# harp_expander_breakout_v1_0.net
KiCad netlist of a schematic drawn in EAGLE
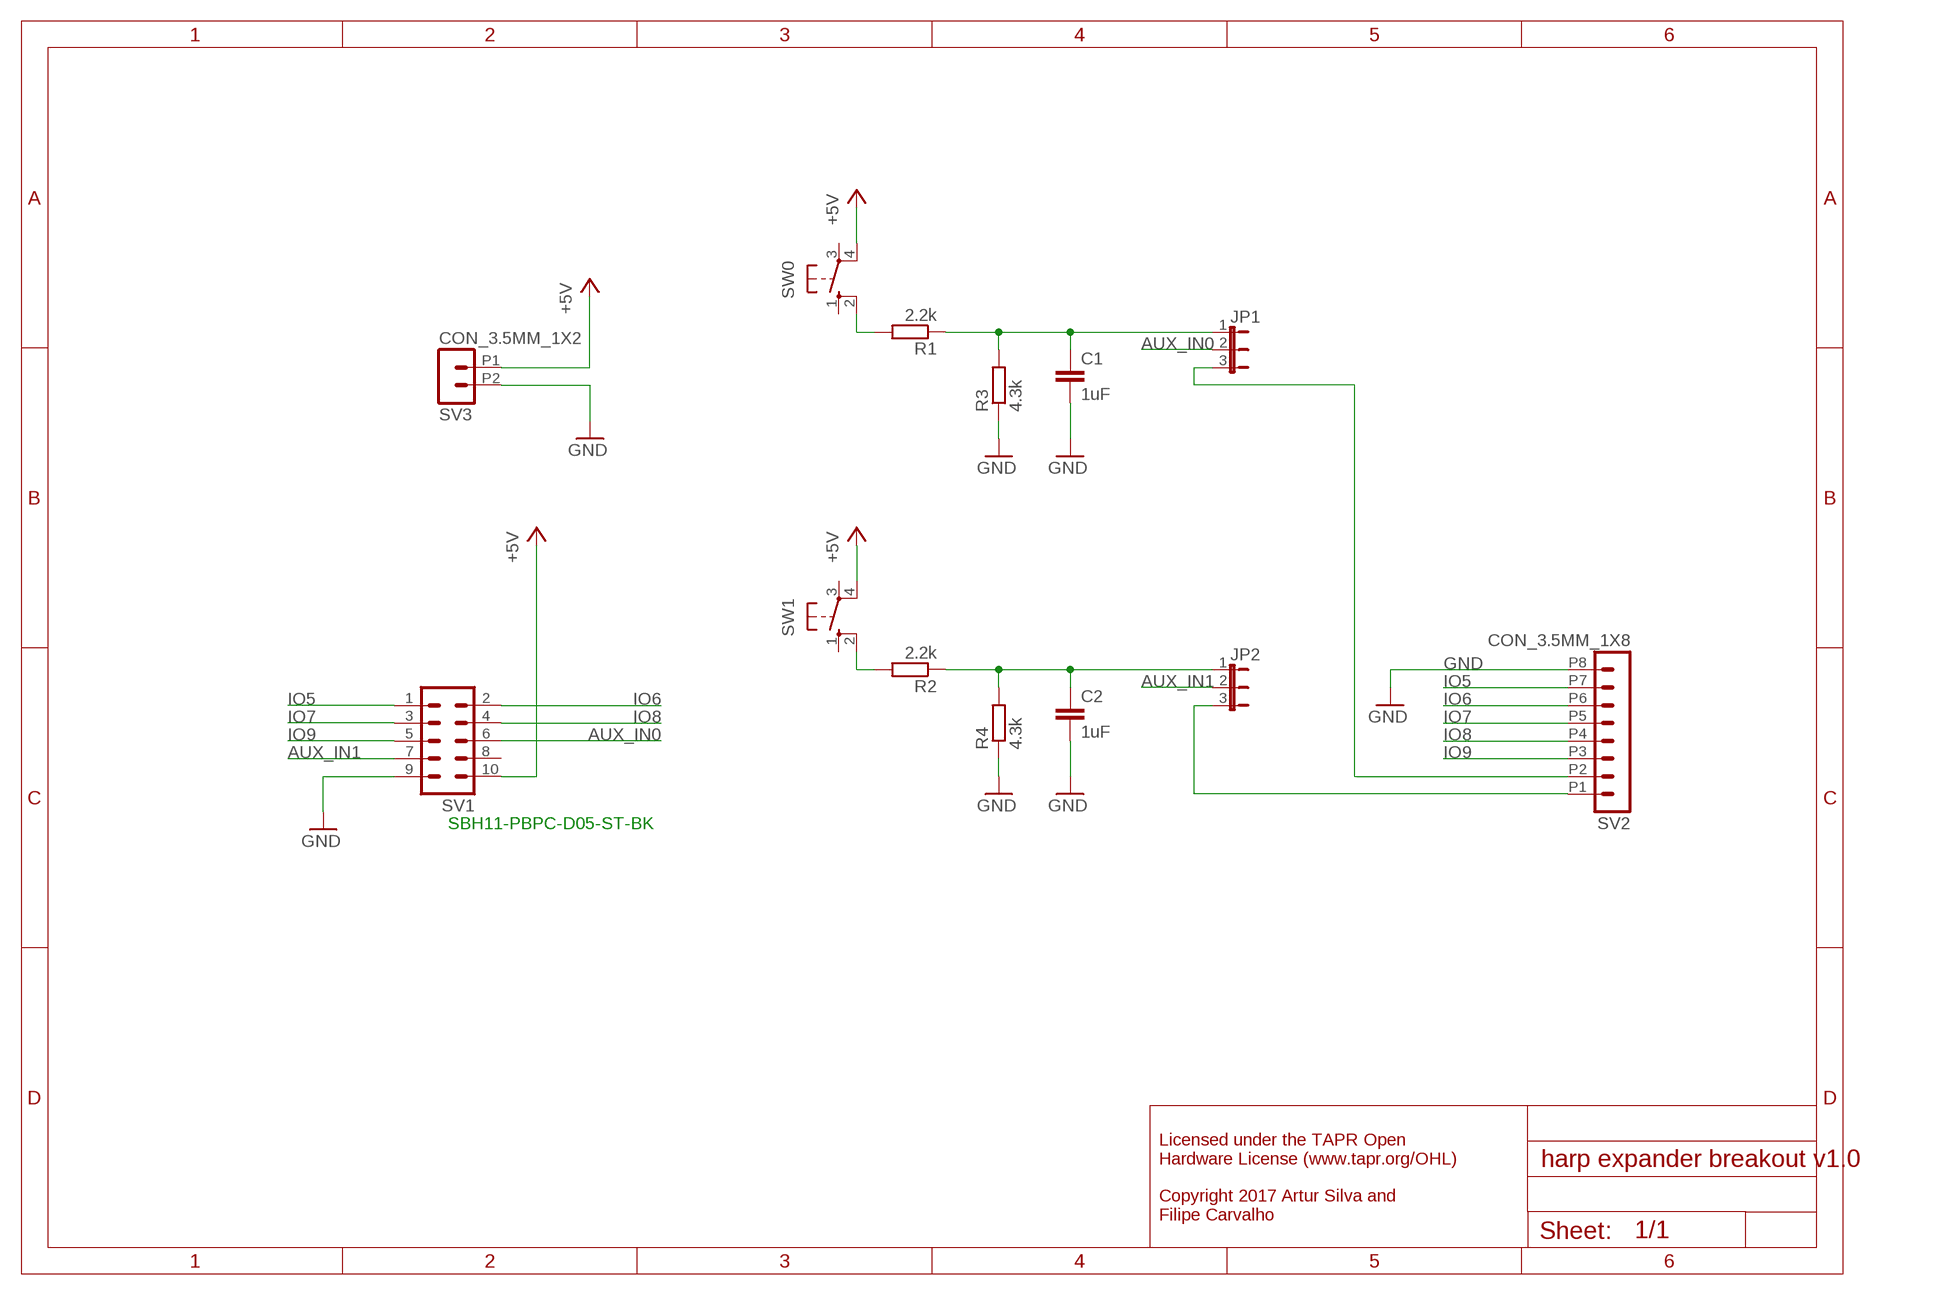
[diagram p0: schematic, sheet 1]

(export (version "E")
  (design (tool "Eeschema 10.0.6"))
  (components
    (comp (ref "C1")
      (value "1uF")
      (footprint "eagle-import:C0603")
      (libsource (lib "eagle-import") (part "C-EUC0603"))
    )
    (comp (ref "C2")
      (value "1uF")
      (footprint "eagle-import:C0603")
      (libsource (lib "eagle-import") (part "C-EUC0603"))
    )
    (comp (ref "JP1")
      (value "JP2E")
      (footprint "eagle-import:JP2")
      (libsource (lib "eagle-import") (part "JP2E"))
    )
    (comp (ref "JP2")
      (value "JP2E")
      (footprint "eagle-import:JP2")
      (libsource (lib "eagle-import") (part "JP2E"))
    )
    (comp (ref "R1")
      (value "2.2k")
      (footprint "eagle-import:R0603")
      (libsource (lib "eagle-import") (part "R-EU_R0603"))
    )
    (comp (ref "R2")
      (value "2.2k")
      (footprint "eagle-import:R0603")
      (libsource (lib "eagle-import") (part "R-EU_R0603"))
    )
    (comp (ref "R3")
      (value "4.3k")
      (footprint "eagle-import:R0603")
      (libsource (lib "eagle-import") (part "R-EU_R0603"))
    )
    (comp (ref "R4")
      (value "4.3k")
      (footprint "eagle-import:R0603")
      (libsource (lib "eagle-import") (part "R-EU_R0603"))
    )
    (comp (ref "SV1")
      (value "ML10")
      (footprint "eagle-import:ML10")
      (libsource (lib "eagle-import") (part "ML10"))
    )
    (comp (ref "SV2")
      (value "CON_3.5MM_1X8")
      (footprint "eagle-import:CON_3.5MM_1X8")
      (libsource (lib "eagle-import") (part "CON_3.5MM_1X8"))
    )
    (comp (ref "SV3")
      (value "CON_3.5MM_1X2")
      (footprint "eagle-import:CON_3.5MM_1X2")
      (libsource (lib "eagle-import") (part "CON_3.5MM_1X2"))
    )
    (comp (ref "SW0")
      (value "40-XX")
      (footprint "eagle-import:B3F-40XX")
      (fields
        (field (name "MF") "OMRON COMPONENTS USA")
        (field (name "MPN") "B3F-4000")
        (field (name "MF_1") "OMRON COMPONENTS USA")
        (field (name "MPN_1") "B3F-4000")
        (field (name "OC_FARNELL") "176434")
        (field (name "OC_NEWARK") "36K3105")
      )
      (libsource (lib "eagle-import") (part "40-XX"))
    )
    (comp (ref "SW1")
      (value "40-XX")
      (footprint "eagle-import:B3F-40XX")
      (fields (field (name "MF") "OMRON COMPONENTS USA") (field (name "MPN") "B3F-4000"))
      (libsource (lib "eagle-import") (part "40-XX"))
    )
  )
  (nets
    (net (code "1") (name "+5V") (class "Default")
      (node (ref "SV1") (pin "10") (pinfunction "10_10") (pintype "passive"))
      (node (ref "SV3") (pin "P1") (pinfunction "1_P1") (pintype "passive"))
      (node (ref "SW0") (pin "4") (pinfunction "P1_4") (pintype "passive"))
      (node (ref "SW1") (pin "4") (pinfunction "P1_4") (pintype "passive"))
    )
    (net (code "2") (name "/AUX_IN0") (class "Default")
      (node (ref "JP1") (pin "2") (pinfunction "2_2") (pintype "passive"))
      (node (ref "SV1") (pin "6") (pinfunction "6_6") (pintype "passive"))
    )
    (net (code "3") (name "/AUX_IN1") (class "Default")
      (node (ref "JP2") (pin "2") (pinfunction "2_2") (pintype "passive"))
      (node (ref "SV1") (pin "7") (pinfunction "7_7") (pintype "passive"))
    )
    (net (code "4") (name "/IO5") (class "Default")
      (node (ref "SV1") (pin "1") (pinfunction "1_1") (pintype "passive"))
      (node (ref "SV2") (pin "P7") (pinfunction "7_P7") (pintype "passive"))
    )
    (net (code "5") (name "/IO6") (class "Default")
      (node (ref "SV1") (pin "2") (pinfunction "2_2") (pintype "passive"))
      (node (ref "SV2") (pin "P6") (pinfunction "6_P6") (pintype "passive"))
    )
    (net (code "6") (name "/IO7") (class "Default")
      (node (ref "SV1") (pin "3") (pinfunction "3_3") (pintype "passive"))
      (node (ref "SV2") (pin "P5") (pinfunction "5_P5") (pintype "passive"))
    )
    (net (code "7") (name "/IO8") (class "Default")
      (node (ref "SV1") (pin "4") (pinfunction "4_4") (pintype "passive"))
      (node (ref "SV2") (pin "P4") (pinfunction "4_P4") (pintype "passive"))
    )
    (net (code "8") (name "/IO9") (class "Default")
      (node (ref "SV1") (pin "5") (pinfunction "5_5") (pintype "passive"))
      (node (ref "SV2") (pin "P3") (pinfunction "3_P3") (pintype "passive"))
    )
    (net (code "9") (name "GND") (class "Default")
      (node (ref "C1") (pin "2") (pinfunction "2_2") (pintype "passive"))
      (node (ref "C2") (pin "2") (pinfunction "2_2") (pintype "passive"))
      (node (ref "R3") (pin "1") (pinfunction "1_1") (pintype "passive"))
      (node (ref "R4") (pin "1") (pinfunction "1_1") (pintype "passive"))
      (node (ref "SV1") (pin "9") (pinfunction "9_9") (pintype "passive"))
      (node (ref "SV2") (pin "P8") (pinfunction "8_P8") (pintype "passive"))
      (node (ref "SV3") (pin "P2") (pinfunction "2_P2") (pintype "passive"))
    )
    (net (code "10") (name "Net-(C1-Pad1)") (class "Default")
      (node (ref "C1") (pin "1") (pinfunction "1_1") (pintype "passive"))
      (node (ref "JP1") (pin "1") (pinfunction "1_1") (pintype "passive"))
      (node (ref "R1") (pin "1") (pinfunction "1_1") (pintype "passive"))
      (node (ref "R3") (pin "2") (pinfunction "2_2") (pintype "passive"))
    )
    (net (code "11") (name "Net-(C2-Pad1)") (class "Default")
      (node (ref "C2") (pin "1") (pinfunction "1_1") (pintype "passive"))
      (node (ref "JP2") (pin "1") (pinfunction "1_1") (pintype "passive"))
      (node (ref "R2") (pin "1") (pinfunction "1_1") (pintype "passive"))
      (node (ref "R4") (pin "2") (pinfunction "2_2") (pintype "passive"))
    )
    (net (code "12") (name "Net-(SV2-1)") (class "Default")
      (node (ref "JP2") (pin "3") (pinfunction "3_3") (pintype "passive"))
      (node (ref "SV2") (pin "P1") (pinfunction "1_P1") (pintype "passive"))
    )
    (net (code "13") (name "Net-(SV2-2)") (class "Default")
      (node (ref "JP1") (pin "3") (pinfunction "3_3") (pintype "passive"))
      (node (ref "SV2") (pin "P2") (pinfunction "2_P2") (pintype "passive"))
    )
    (net (code "14") (name "Net-(SW0-S1)") (class "Default")
      (node (ref "R1") (pin "2") (pinfunction "2_2") (pintype "passive"))
      (node (ref "SW0") (pin "2") (pinfunction "S1_2") (pintype "passive"))
    )
    (net (code "15") (name "Net-(SW1-S1)") (class "Default")
      (node (ref "R2") (pin "2") (pinfunction "2_2") (pintype "passive"))
      (node (ref "SW1") (pin "2") (pinfunction "S1_2") (pintype "passive"))
    )
    (net (code "16") (name "unconnected-(SV1-Pad8)") (class "Default")
      (node (ref "SV1") (pin "8") (pinfunction "8_8") (pintype "passive"))
    )
    (net (code "17") (name "unconnected-(SW0-P-Pad3)") (class "Default")
      (node (ref "SW0") (pin "3") (pinfunction "P_3") (pintype "passive"))
    )
    (net (code "18") (name "unconnected-(SW0-S-Pad1)") (class "Default")
      (node (ref "SW0") (pin "1") (pinfunction "S_1") (pintype "passive"))
    )
    (net (code "19") (name "unconnected-(SW1-P-Pad3)") (class "Default")
      (node (ref "SW1") (pin "3") (pinfunction "P_3") (pintype "passive"))
    )
    (net (code "20") (name "unconnected-(SW1-S-Pad1)") (class "Default")
      (node (ref "SW1") (pin "1") (pinfunction "S_1") (pintype "passive"))
    )
  )
)
